# SparkFun_GPS_NEO_M9N_SMA__LONG.net
KiCad netlist of a schematic drawn in EAGLE
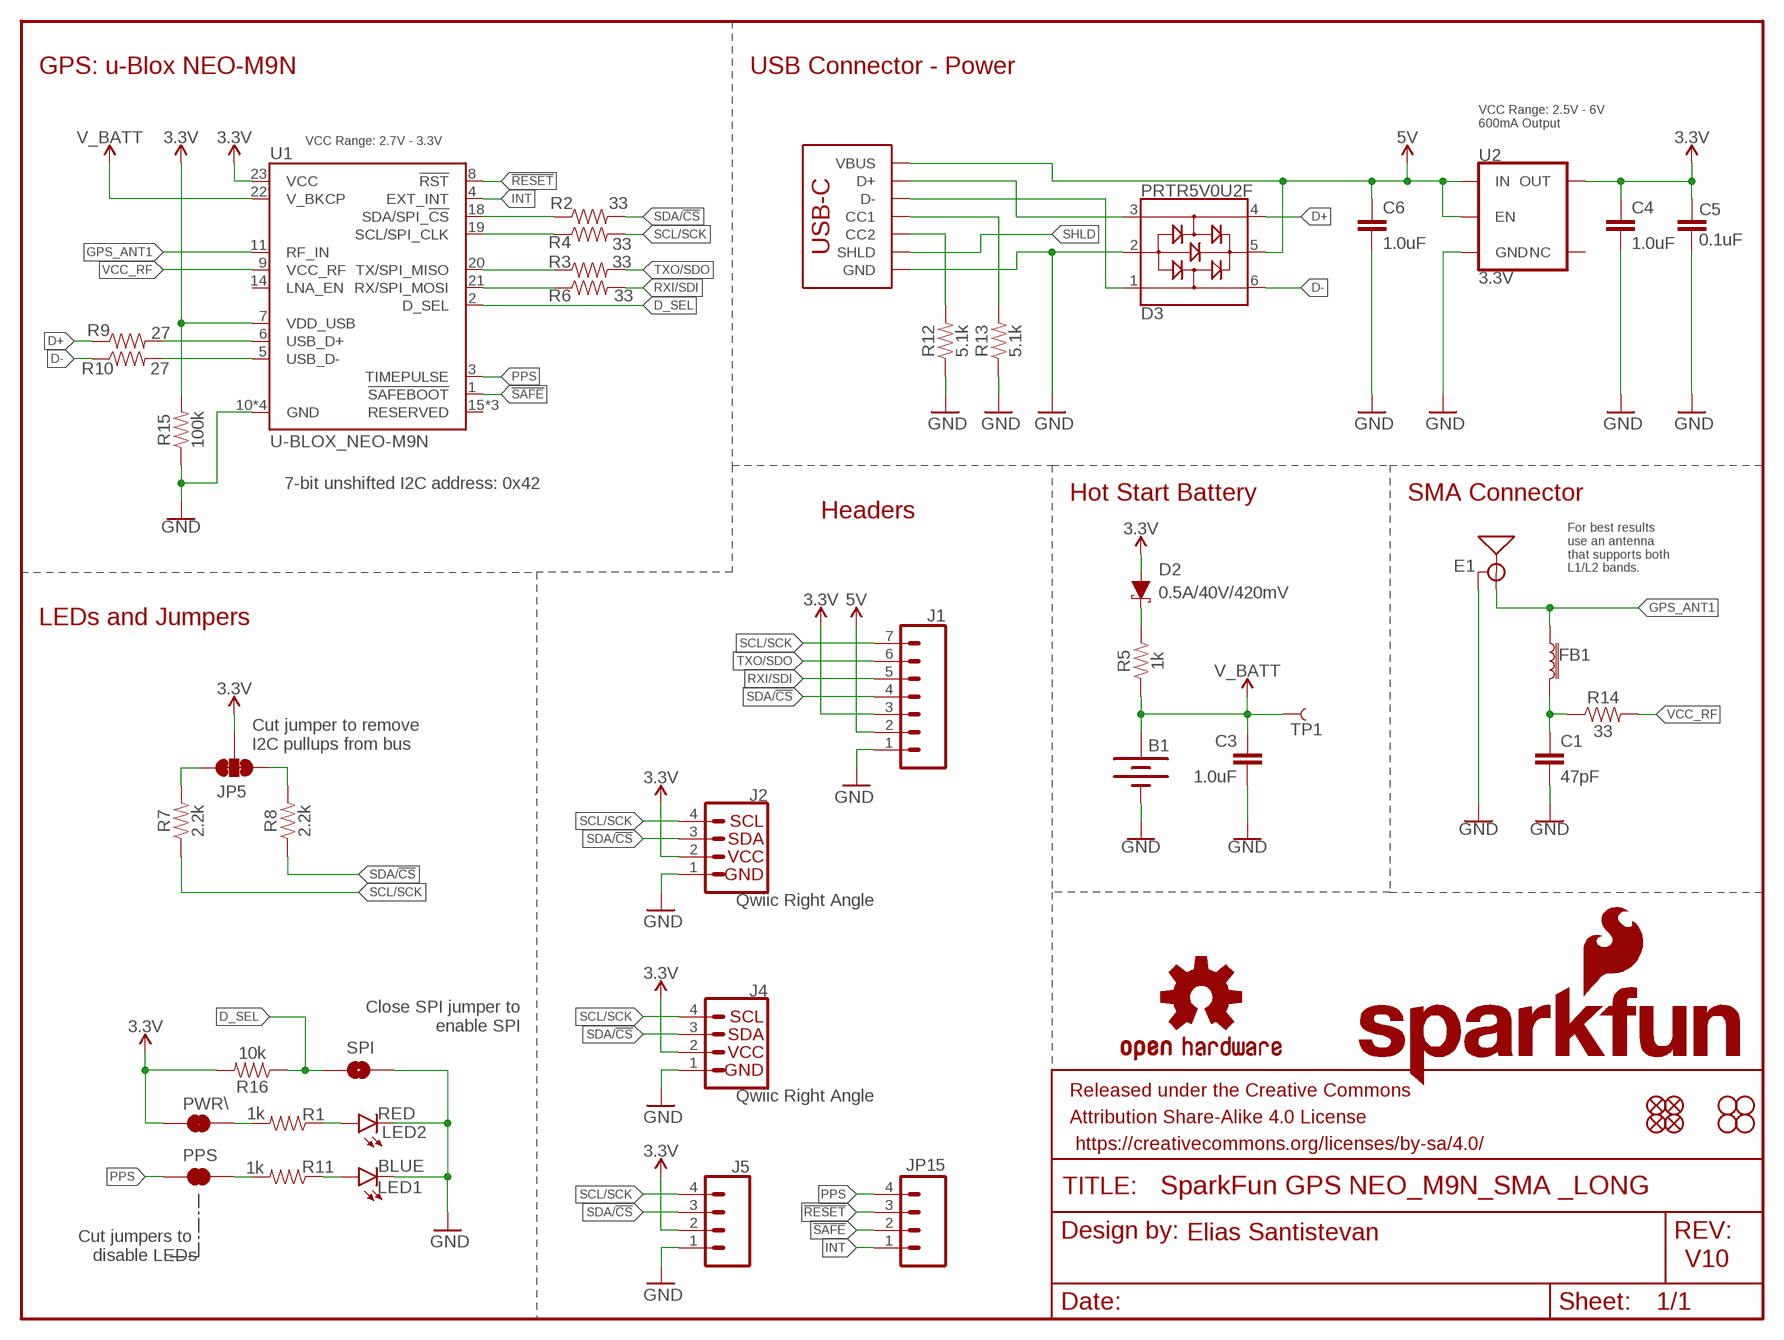
[diagram p0: schematic, sheet 1]

(export (version "E")
  (design (tool "Eeschema 10.0.6"))
  (components
    (comp (ref "B1")
      (value "6.8MM_COIN_CELL")
      (footprint "eagle-import:ML414H_IV01E")
      (libsource (lib "eagle-import") (part "ML414H_IV01E_BATTERY"))
    )
    (comp (ref "C1")
      (value "47pF")
      (footprint "eagle-import:0402")
      (libsource (lib "eagle-import") (part "47PF-0402-25V-5%-X7R"))
    )
    (comp (ref "C3")
      (value "1.0uF")
      (footprint "eagle-import:0603")
      (libsource (lib "eagle-import") (part "1.0UF-0603-16V-10%"))
    )
    (comp (ref "C4")
      (value "1.0uF")
      (footprint "eagle-import:0603")
      (libsource (lib "eagle-import") (part "1.0UF-0603-16V-10%"))
    )
    (comp (ref "C5")
      (value "0.1uF")
      (footprint "eagle-import:0603")
      (libsource (lib "eagle-import") (part "0.1UF-0603-25V-(+80/-20%)"))
    )
    (comp (ref "C6")
      (value "1.0uF")
      (footprint "eagle-import:0603")
      (libsource (lib "eagle-import") (part "1.0UF-0603-16V-10%"))
    )
    (comp (ref "D2")
      (value "0.5A/40V/420mV")
      (footprint "eagle-import:SOD-323")
      (libsource (lib "eagle-import") (part "DIODE-SCHOTTKY-PMEG4005EJ"))
    )
    (comp (ref "D3")
      (value "PRTR5V0U2F")
      (footprint "eagle-import:SOT886")
      (libsource (lib "eagle-import") (part "PRTR5V0U2F"))
    )
    (comp (ref "E1")
      (value "ANTENNA-GROUNDEDEDGE_RPSMA_SMD")
      (footprint "eagle-import:SMA-EDGE-SMD")
      (libsource (lib "eagle-import") (part "ANTENNA-GROUNDEDEDGE_RPSMA_SMD"))
    )
    (comp (ref "FB1")
      (value "FERRITE_BEAD-120_OHM-0402")
      (footprint "eagle-import:0402")
      (fields (field (name "MFG_PART") "BLM15HB121SN1D"))
      (libsource (lib "eagle-import") (part "FERRITE_BEAD-120_OHM-0402"))
    )
    (comp (ref "FRAME1")
      (value "FRAME-LETTER")
      (footprint "eagle-import:CREATIVE_COMMONS")
      (libsource (lib "eagle-import") (part "FRAME-LETTER"))
    )
    (comp (ref "J1")
      (value "CONN_07NO_SILK")
      (footprint "eagle-import:1X07_NO_SILK")
      (libsource (lib "eagle-import") (part "CONN_07NO_SILK"))
    )
    (comp (ref "J2")
      (value "Qwiic Right Angle")
      (footprint "eagle-import:JST04_1MM_RA")
      (libsource (lib "eagle-import") (part "I2C_STANDARDQWIIC"))
    )
    (comp (ref "J3")
      (value "USB_C_2-LAYER_PADS")
      (footprint "eagle-import:USB-C-16P-2LAYER-PADS")
      (libsource (lib "eagle-import") (part "USB_C_2-LAYER_PADS"))
    )
    (comp (ref "J4")
      (value "Qwiic Right Angle")
      (footprint "eagle-import:JST04_1MM_RA")
      (libsource (lib "eagle-import") (part "I2C_STANDARDQWIIC"))
    )
    (comp (ref "J5")
      (value "CONN_041X04_NO_SILK_NO_POP")
      (footprint "eagle-import:1X04_NO_SILK")
      (libsource (lib "eagle-import") (part "CONN_041X04_NO_SILK_NO_POP"))
    )
    (comp (ref "JP1")
      (value "STAND-OFF")
      (footprint "eagle-import:STAND-OFF")
      (libsource (lib "eagle-import") (part "STAND-OFF"))
    )
    (comp (ref "JP5")
      (value "JUMPER-SMT_3_2-NC_TRACE_SILK")
      (footprint "eagle-import:SMT-JUMPER_3_2-NC_TRACE_SILK")
      (libsource (lib "eagle-import") (part "JUMPER-SMT_3_2-NC_TRACE_SILK"))
    )
    (comp (ref "JP15")
      (value "CONN_041X04_NO_SILK_NO_POP")
      (footprint "eagle-import:1X04_NO_SILK")
      (libsource (lib "eagle-import") (part "CONN_041X04_NO_SILK_NO_POP"))
    )
    (comp (ref "JP21")
      (value "FIDUCIALUFIDUCIAL")
      (footprint "eagle-import:MICRO-FIDUCIAL")
      (libsource (lib "eagle-import") (part "FIDUCIALUFIDUCIAL"))
    )
    (comp (ref "JP31")
      (value "STAND-OFF")
      (footprint "eagle-import:STAND-OFF")
      (libsource (lib "eagle-import") (part "STAND-OFF"))
    )
    (comp (ref "JP61")
      (value "FIDUCIALUFIDUCIAL")
      (footprint "eagle-import:MICRO-FIDUCIAL")
      (libsource (lib "eagle-import") (part "FIDUCIALUFIDUCIAL"))
    )
    (comp (ref "JP71")
      (value "FIDUCIALUFIDUCIAL")
      (footprint "eagle-import:MICRO-FIDUCIAL")
      (libsource (lib "eagle-import") (part "FIDUCIALUFIDUCIAL"))
    )
    (comp (ref "JP81")
      (value "FIDUCIALUFIDUCIAL")
      (footprint "eagle-import:MICRO-FIDUCIAL")
      (libsource (lib "eagle-import") (part "FIDUCIALUFIDUCIAL"))
    )
    (comp (ref "JP91")
      (value "STAND-OFF")
      (footprint "eagle-import:STAND-OFF")
      (libsource (lib "eagle-import") (part "STAND-OFF"))
    )
    (comp (ref "JP101")
      (value "STAND-OFF")
      (footprint "eagle-import:STAND-OFF")
      (libsource (lib "eagle-import") (part "STAND-OFF"))
    )
    (comp (ref "LED1")
      (value "BLUE")
      (footprint "eagle-import:LED-0603")
      (libsource (lib "eagle-import") (part "LED-BLUE0603"))
    )
    (comp (ref "LED2")
      (value "RED")
      (footprint "eagle-import:LED-0603")
      (libsource (lib "eagle-import") (part "LED-RED0603"))
    )
    (comp (ref "LOGO1")
      (value "OSHW-LOGOMINI")
      (footprint "eagle-import:OSHW-LOGO-MINI")
      (libsource (lib "eagle-import") (part "OSHW-LOGOMINI"))
    )
    (comp (ref "LOGO2")
      (value "SFE_LOGO_NAME_FLAME.1_INCH")
      (footprint "eagle-import:SFE_LOGO_NAME_FLAME_.1")
      (libsource (lib "eagle-import") (part "SFE_LOGO_NAME_FLAME.1_INCH"))
    )
    (comp (ref "PPS")
      (value "JUMPER-SMT_2_NC_TRACE_SILK")
      (footprint "eagle-import:SMT-JUMPER_2_NC_TRACE_SILK")
      (libsource (lib "eagle-import") (part "JUMPER-SMT_2_NC_TRACE_SILK"))
    )
    (comp (ref "PWR\\")
      (value "JUMPER-SMT_2_NC_TRACE_SILK")
      (footprint "eagle-import:SMT-JUMPER_2_NC_TRACE_SILK")
      (libsource (lib "eagle-import") (part "JUMPER-SMT_2_NC_TRACE_SILK"))
    )
    (comp (ref "R1")
      (value "1k")
      (footprint "eagle-import:0603")
      (libsource (lib "eagle-import") (part "1KOHM-0603-1/10W-1%"))
    )
    (comp (ref "R2")
      (value "33")
      (footprint "eagle-import:0603")
      (libsource (lib "eagle-import") (part "33OHM-0603-1/10W-1%"))
    )
    (comp (ref "R3")
      (value "33")
      (footprint "eagle-import:0603")
      (libsource (lib "eagle-import") (part "33OHM-0603-1/10W-1%"))
    )
    (comp (ref "R4")
      (value "33")
      (footprint "eagle-import:0603")
      (libsource (lib "eagle-import") (part "33OHM-0603-1/10W-1%"))
    )
    (comp (ref "R5")
      (value "1k")
      (footprint "eagle-import:0603")
      (libsource (lib "eagle-import") (part "1KOHM-0603-1/10W-1%"))
    )
    (comp (ref "R6")
      (value "33")
      (footprint "eagle-import:0603")
      (libsource (lib "eagle-import") (part "33OHM-0603-1/10W-1%"))
    )
    (comp (ref "R7")
      (value "2.2k")
      (footprint "eagle-import:0603")
      (libsource (lib "eagle-import") (part "2.2KOHM-0603-1/10W-1%"))
    )
    (comp (ref "R8")
      (value "2.2k")
      (footprint "eagle-import:0603")
      (libsource (lib "eagle-import") (part "2.2KOHM-0603-1/10W-1%"))
    )
    (comp (ref "R9")
      (value "27")
      (footprint "eagle-import:0603")
      (libsource (lib "eagle-import") (part "27OHM-0603-1/10W-1%"))
    )
    (comp (ref "R10")
      (value "27")
      (footprint "eagle-import:0603")
      (libsource (lib "eagle-import") (part "27OHM-0603-1/10W-1%"))
    )
    (comp (ref "R11")
      (value "1k")
      (footprint "eagle-import:0603")
      (libsource (lib "eagle-import") (part "1KOHM-0603-1/10W-1%"))
    )
    (comp (ref "R12")
      (value "5.1k")
      (footprint "eagle-import:0603")
      (libsource (lib "eagle-import") (part "5.1KOHM5.1KOHM-0603-1/10W-1%"))
    )
    (comp (ref "R13")
      (value "5.1k")
      (footprint "eagle-import:0603")
      (libsource (lib "eagle-import") (part "5.1KOHM5.1KOHM-0603-1/10W-1%"))
    )
    (comp (ref "R14")
      (value "33")
      (footprint "eagle-import:0402")
      (libsource (lib "eagle-import") (part "33OHM-0402-1/10W-1%"))
    )
    (comp (ref "R15")
      (value "100k")
      (footprint "eagle-import:0603")
      (libsource (lib "eagle-import") (part "100KOHM-0603-1/10W-1%"))
    )
    (comp (ref "R16")
      (value "10k")
      (footprint "eagle-import:0402")
      (libsource (lib "eagle-import") (part "10KOHM-0402-1/16W-1%"))
    )
    (comp (ref "SPI")
      (value "JUMPER-SMT_2_NO_SILK")
      (footprint "eagle-import:SMT-JUMPER_2_NO_SILK")
      (libsource (lib "eagle-import") (part "JUMPER-SMT_2_NO_SILK"))
    )
    (comp (ref "TP1")
      (value "TEST-POINT3X4")
      (footprint "eagle-import:PAD.03X.04")
      (libsource (lib "eagle-import") (part "TEST-POINT3X4"))
    )
    (comp (ref "U1")
      (value "U-BLOX_NEO-M9N")
      (footprint "eagle-import:NEO-M9N_M8T_M8U")
      (libsource (lib "eagle-import") (part "U-BLOX_NEO-M9N"))
    )
    (comp (ref "U2")
      (value "3.3V")
      (footprint "eagle-import:SOT23-5")
      (libsource (lib "eagle-import") (part "V_REG_AP2112K-3.3V"))
    )
  )
  (nets
    (net (code "1") (name "/SDA{slash}~{CS}") (class "Default")
      (node (ref "J1") (pin "4") (pinfunction "4_4") (pintype "passive"))
      (node (ref "J2") (pin "3") (pinfunction "3_3") (pintype "passive"))
      (node (ref "J4") (pin "3") (pinfunction "3_3") (pintype "passive"))
      (node (ref "J5") (pin "3") (pinfunction "3_3") (pintype "passive"))
      (node (ref "R2") (pin "2") (pinfunction "2_2") (pintype "passive"))
      (node (ref "R8") (pin "1") (pinfunction "1_1") (pintype "passive"))
    )
    (net (code "2") (name "/~{RESET}") (class "Default")
      (node (ref "JP15") (pin "3") (pinfunction "3_3") (pintype "passive"))
      (node (ref "U1") (pin "8") (pinfunction "~{RST}_8") (pintype "bidirectional"))
    )
    (net (code "3") (name "/~{SAFE}") (class "Default")
      (node (ref "JP15") (pin "2") (pinfunction "2_2") (pintype "passive"))
      (node (ref "U1") (pin "1") (pinfunction "~{SAFEBOOT}_1") (pintype "bidirectional"))
    )
    (net (code "4") (name "3.3V") (class "Default")
      (node (ref "C4") (pin "1") (pinfunction "1_1") (pintype "passive"))
      (node (ref "C5") (pin "2") (pinfunction "2_2") (pintype "passive"))
      (node (ref "D2") (pin "A") (pinfunction "A_A") (pintype "passive"))
      (node (ref "J1") (pin "3") (pinfunction "3_3") (pintype "passive"))
      (node (ref "J2") (pin "2") (pinfunction "2_2") (pintype "power_in"))
      (node (ref "J4") (pin "2") (pinfunction "2_2") (pintype "power_in"))
      (node (ref "J5") (pin "2") (pinfunction "2_2") (pintype "passive"))
      (node (ref "JP5") (pin "2") (pinfunction "2_2") (pintype "passive"))
      (node (ref "PWR\\") (pin "2") (pinfunction "2_2") (pintype "passive"))
      (node (ref "R15") (pin "2") (pinfunction "2_2") (pintype "passive"))
      (node (ref "R16") (pin "2") (pinfunction "2_2") (pintype "passive"))
      (node (ref "U1") (pin "23") (pinfunction "VCC_23") (pintype "bidirectional"))
      (node (ref "U1") (pin "7") (pinfunction "VDD_USB_7") (pintype "bidirectional"))
      (node (ref "U2") (pin "5") (pinfunction "OUT_5") (pintype "passive"))
    )
    (net (code "5") (name "5V") (class "Default")
      (node (ref "C6") (pin "1") (pinfunction "1_1") (pintype "passive"))
      (node (ref "D3") (pin "5") (pinfunction "5_5") (pintype "bidirectional"))
      (node (ref "J1") (pin "2") (pinfunction "2_2") (pintype "passive"))
      (node (ref "J3") (pin "VBUS1") (pinfunction "VBUS_VBUS1") (pintype "bidirectional"))
      (node (ref "J3") (pin "VBUS2") (pinfunction "VBUS_VBUS2") (pintype "bidirectional"))
      (node (ref "U2") (pin "1") (pinfunction "IN_1") (pintype "input"))
      (node (ref "U2") (pin "3") (pinfunction "EN_3") (pintype "input"))
    )
    (net (code "6") (name "D+") (class "Default")
      (node (ref "D3") (pin "4") (pinfunction "4_4") (pintype "bidirectional"))
      (node (ref "R9") (pin "1") (pinfunction "1_1") (pintype "passive"))
    )
    (net (code "7") (name "D-") (class "Default")
      (node (ref "D3") (pin "6") (pinfunction "6_6") (pintype "bidirectional"))
      (node (ref "R10") (pin "1") (pinfunction "1_1") (pintype "passive"))
    )
    (net (code "8") (name "D_SEL") (class "Default")
      (node (ref "R16") (pin "1") (pinfunction "1_1") (pintype "passive"))
      (node (ref "SPI") (pin "2") (pinfunction "2_2") (pintype "passive"))
      (node (ref "U1") (pin "2") (pinfunction "D_SEL_2") (pintype "bidirectional"))
    )
    (net (code "9") (name "GND") (class "Default")
      (node (ref "B1") (pin "-") (pinfunction "-_-") (pintype "power_in"))
      (node (ref "C1") (pin "2") (pinfunction "2_2") (pintype "passive"))
      (node (ref "C3") (pin "2") (pinfunction "2_2") (pintype "passive"))
      (node (ref "C4") (pin "2") (pinfunction "2_2") (pintype "passive"))
      (node (ref "C5") (pin "1") (pinfunction "1_1") (pintype "passive"))
      (node (ref "C6") (pin "2") (pinfunction "2_2") (pintype "passive"))
      (node (ref "D3") (pin "2") (pinfunction "2_2") (pintype "bidirectional"))
      (node (ref "E1") (pin "GND@0") (pinfunction "GND_GND@0") (pintype "bidirectional"))
      (node (ref "E1") (pin "GND@1") (pinfunction "GND_GND@1") (pintype "bidirectional"))
      (node (ref "J1") (pin "1") (pinfunction "1_1") (pintype "passive"))
      (node (ref "J2") (pin "1") (pinfunction "1_1") (pintype "power_in"))
      (node (ref "J3") (pin "GND") (pinfunction "GND_GND") (pintype "bidirectional"))
      (node (ref "J3") (pin "GND2") (pinfunction "GND_GND2") (pintype "bidirectional"))
      (node (ref "J4") (pin "1") (pinfunction "1_1") (pintype "power_in"))
      (node (ref "J5") (pin "1") (pinfunction "1_1") (pintype "passive"))
      (node (ref "LED1") (pin "C") (pinfunction "C_C") (pintype "passive"))
      (node (ref "LED2") (pin "C") (pinfunction "C_C") (pintype "passive"))
      (node (ref "R12") (pin "1") (pinfunction "1_1") (pintype "passive"))
      (node (ref "R13") (pin "1") (pinfunction "1_1") (pintype "passive"))
      (node (ref "R15") (pin "1") (pinfunction "1_1") (pintype "passive"))
      (node (ref "SPI") (pin "1") (pinfunction "1_1") (pintype "passive"))
      (node (ref "U1") (pin "10") (pinfunction "GND_10") (pintype "bidirectional"))
      (node (ref "U1") (pin "12") (pinfunction "GND_12") (pintype "bidirectional"))
      (node (ref "U1") (pin "13") (pinfunction "GND_13") (pintype "bidirectional"))
      (node (ref "U1") (pin "24") (pinfunction "GND_24") (pintype "bidirectional"))
      (node (ref "U2") (pin "2") (pinfunction "GND_2") (pintype "input"))
    )
    (net (code "10") (name "GPS_ANT1") (class "Default")
      (node (ref "E1") (pin "SIG") (pinfunction "SIGNAL_SIG") (pintype "bidirectional"))
      (node (ref "FB1") (pin "1") (pinfunction "1_1") (pintype "passive"))
      (node (ref "U1") (pin "11") (pinfunction "RF_IN_11") (pintype "bidirectional"))
    )
    (net (code "11") (name "INT") (class "Default")
      (node (ref "JP15") (pin "1") (pinfunction "1_1") (pintype "passive"))
      (node (ref "U1") (pin "4") (pinfunction "EXT_INT_4") (pintype "bidirectional"))
    )
    (net (code "12") (name "Net-(C1-Pad1)") (class "Default")
      (node (ref "C1") (pin "1") (pinfunction "1_1") (pintype "passive"))
      (node (ref "FB1") (pin "2") (pinfunction "2_2") (pintype "passive"))
      (node (ref "R14") (pin "1") (pinfunction "1_1") (pintype "passive"))
    )
    (net (code "13") (name "Net-(D2-PadC)") (class "Default")
      (node (ref "D2") (pin "C") (pinfunction "C_C") (pintype "passive"))
      (node (ref "R5") (pin "2") (pinfunction "2_2") (pintype "passive"))
    )
    (net (code "14") (name "Net-(D3-Pad1)") (class "Default")
      (node (ref "D3") (pin "1") (pinfunction "1_1") (pintype "bidirectional"))
      (node (ref "J3") (pin "A7") (pinfunction "D-_A7") (pintype "bidirectional"))
      (node (ref "J3") (pin "B7") (pinfunction "D-_B7") (pintype "bidirectional"))
    )
    (net (code "15") (name "Net-(D3-Pad3)") (class "Default")
      (node (ref "D3") (pin "3") (pinfunction "3_3") (pintype "bidirectional"))
      (node (ref "J3") (pin "A6") (pinfunction "D+_A6") (pintype "bidirectional"))
      (node (ref "J3") (pin "B6") (pinfunction "D+_B6") (pintype "bidirectional"))
    )
    (net (code "16") (name "Net-(J3-CC1)") (class "Default")
      (node (ref "J3") (pin "A5") (pinfunction "CC1_A5") (pintype "bidirectional"))
      (node (ref "R13") (pin "2") (pinfunction "2_2") (pintype "passive"))
    )
    (net (code "17") (name "Net-(J3-CC2)") (class "Default")
      (node (ref "J3") (pin "B5") (pinfunction "CC2_B5") (pintype "bidirectional"))
      (node (ref "R12") (pin "2") (pinfunction "2_2") (pintype "passive"))
    )
    (net (code "18") (name "Net-(JP5-Pad1)") (class "Default")
      (node (ref "JP5") (pin "1") (pinfunction "1_1") (pintype "passive"))
      (node (ref "R8") (pin "2") (pinfunction "2_2") (pintype "passive"))
    )
    (net (code "19") (name "Net-(JP5-Pad3)") (class "Default")
      (node (ref "JP5") (pin "3") (pinfunction "3_3") (pintype "passive"))
      (node (ref "R7") (pin "2") (pinfunction "2_2") (pintype "passive"))
    )
    (net (code "20") (name "Net-(LED1-PadA)") (class "Default")
      (node (ref "LED1") (pin "A") (pinfunction "A_A") (pintype "passive"))
      (node (ref "R11") (pin "1") (pinfunction "1_1") (pintype "passive"))
    )
    (net (code "21") (name "Net-(LED2-PadA)") (class "Default")
      (node (ref "LED2") (pin "A") (pinfunction "A_A") (pintype "passive"))
      (node (ref "R1") (pin "1") (pinfunction "1_1") (pintype "passive"))
    )
    (net (code "22") (name "Net-(PPS-Pad1)") (class "Default")
      (node (ref "PPS") (pin "1") (pinfunction "1_1") (pintype "passive"))
      (node (ref "R11") (pin "2") (pinfunction "2_2") (pintype "passive"))
    )
    (net (code "23") (name "Net-(PWR\\-Pad1)") (class "Default")
      (node (ref "PWR\\") (pin "1") (pinfunction "1_1") (pintype "passive"))
      (node (ref "R1") (pin "2") (pinfunction "2_2") (pintype "passive"))
    )
    (net (code "24") (name "Net-(U1-RX{slash}SPI_MOSI)") (class "Default")
      (node (ref "R6") (pin "1") (pinfunction "1_1") (pintype "passive"))
      (node (ref "U1") (pin "21") (pinfunction "RX/SPI_MOSI_21") (pintype "bidirectional"))
    )
    (net (code "25") (name "Net-(U1-SCL{slash}SPI_CLK)") (class "Default")
      (node (ref "R4") (pin "1") (pinfunction "1_1") (pintype "passive"))
      (node (ref "U1") (pin "19") (pinfunction "SCL/SPI_CLK_19") (pintype "bidirectional"))
    )
    (net (code "26") (name "Net-(U1-SDA{slash}SPI_~{CS})") (class "Default")
      (node (ref "R2") (pin "1") (pinfunction "1_1") (pintype "passive"))
      (node (ref "U1") (pin "18") (pinfunction "SDA/SPI_~{CS}_18") (pintype "bidirectional"))
    )
    (net (code "27") (name "Net-(U1-TX{slash}SPI_MISO)") (class "Default")
      (node (ref "R3") (pin "1") (pinfunction "1_1") (pintype "passive"))
      (node (ref "U1") (pin "20") (pinfunction "TX/SPI_MISO_20") (pintype "bidirectional"))
    )
    (net (code "28") (name "Net-(U1-USB_D+)") (class "Default")
      (node (ref "R9") (pin "2") (pinfunction "2_2") (pintype "passive"))
      (node (ref "U1") (pin "6") (pinfunction "USB_D+_6") (pintype "bidirectional"))
    )
    (net (code "29") (name "Net-(U1-USB_D-)") (class "Default")
      (node (ref "R10") (pin "2") (pinfunction "2_2") (pintype "passive"))
      (node (ref "U1") (pin "5") (pinfunction "USB_D-_5") (pintype "bidirectional"))
    )
    (net (code "30") (name "PPS") (class "Default")
      (node (ref "JP15") (pin "4") (pinfunction "4_4") (pintype "passive"))
      (node (ref "PPS") (pin "2") (pinfunction "2_2") (pintype "passive"))
      (node (ref "U1") (pin "3") (pinfunction "TIMEPULSE_3") (pintype "bidirectional"))
    )
    (net (code "31") (name "RXI{slash}SDI") (class "Default")
      (node (ref "J1") (pin "5") (pinfunction "5_5") (pintype "passive"))
      (node (ref "R6") (pin "2") (pinfunction "2_2") (pintype "passive"))
    )
    (net (code "32") (name "SCL{slash}SCK") (class "Default")
      (node (ref "J1") (pin "7") (pinfunction "7_7") (pintype "passive"))
      (node (ref "J2") (pin "4") (pinfunction "4_4") (pintype "passive"))
      (node (ref "J4") (pin "4") (pinfunction "4_4") (pintype "passive"))
      (node (ref "J5") (pin "4") (pinfunction "4_4") (pintype "passive"))
      (node (ref "R4") (pin "2") (pinfunction "2_2") (pintype "passive"))
      (node (ref "R7") (pin "1") (pinfunction "1_1") (pintype "passive"))
    )
    (net (code "33") (name "SHLD") (class "Default")
      (node (ref "J3") (pin "SHLD1") (pinfunction "SHLD_SHLD1") (pintype "bidirectional"))
      (node (ref "J3") (pin "SHLD2") (pinfunction "SHLD_SHLD2") (pintype "bidirectional"))
      (node (ref "J3") (pin "SHLD3") (pinfunction "SHLD_SHLD3") (pintype "bidirectional"))
      (node (ref "J3") (pin "SHLD4") (pinfunction "SHLD_SHLD4") (pintype "bidirectional"))
    )
    (net (code "34") (name "TXO{slash}SDO") (class "Default")
      (node (ref "J1") (pin "6") (pinfunction "6_6") (pintype "passive"))
      (node (ref "R3") (pin "2") (pinfunction "2_2") (pintype "passive"))
    )
    (net (code "35") (name "VCC_RF") (class "Default")
      (node (ref "R14") (pin "2") (pinfunction "2_2") (pintype "passive"))
      (node (ref "U1") (pin "9") (pinfunction "VCC_RF_9") (pintype "bidirectional"))
    )
    (net (code "36") (name "V_BATT") (class "Default")
      (node (ref "B1") (pin "+") (pinfunction "+_+") (pintype "power_in"))
      (node (ref "C3") (pin "1") (pinfunction "1_1") (pintype "passive"))
      (node (ref "R5") (pin "1") (pinfunction "1_1") (pintype "passive"))
      (node (ref "TP1") (pin "P$1") (pinfunction "1_P$1") (pintype "bidirectional"))
      (node (ref "U1") (pin "22") (pinfunction "V_BKCP_22") (pintype "bidirectional"))
    )
    (net (code "37") (name "unconnected-(U1-LNA_EN-Pad14)") (class "Default")
      (node (ref "U1") (pin "14") (pinfunction "LNA_EN_14") (pintype "bidirectional"))
    )
    (net (code "38") (name "unconnected-(U1-RESERVED-Pad15)") (class "Default")
      (node (ref "U1") (pin "15") (pinfunction "RESERVED_15") (pintype "no_connect"))
    )
    (net (code "39") (name "unconnected-(U1-RESERVED-Pad16)") (class "Default")
      (node (ref "U1") (pin "16") (pinfunction "RESERVED_16") (pintype "no_connect"))
    )
    (net (code "40") (name "unconnected-(U1-RESERVED-Pad17)") (class "Default")
      (node (ref "U1") (pin "17") (pinfunction "RESERVED_17") (pintype "no_connect"))
    )
    (net (code "41") (name "unconnected-(U2-NC-Pad4)") (class "Default")
      (node (ref "U2") (pin "4") (pinfunction "NC_4") (pintype "no_connect"))
    )
  )
)
